# Output_Register_Electronic_Scheme_2021-1.net
KiCad netlist of a schematic drawn in Altium Designer
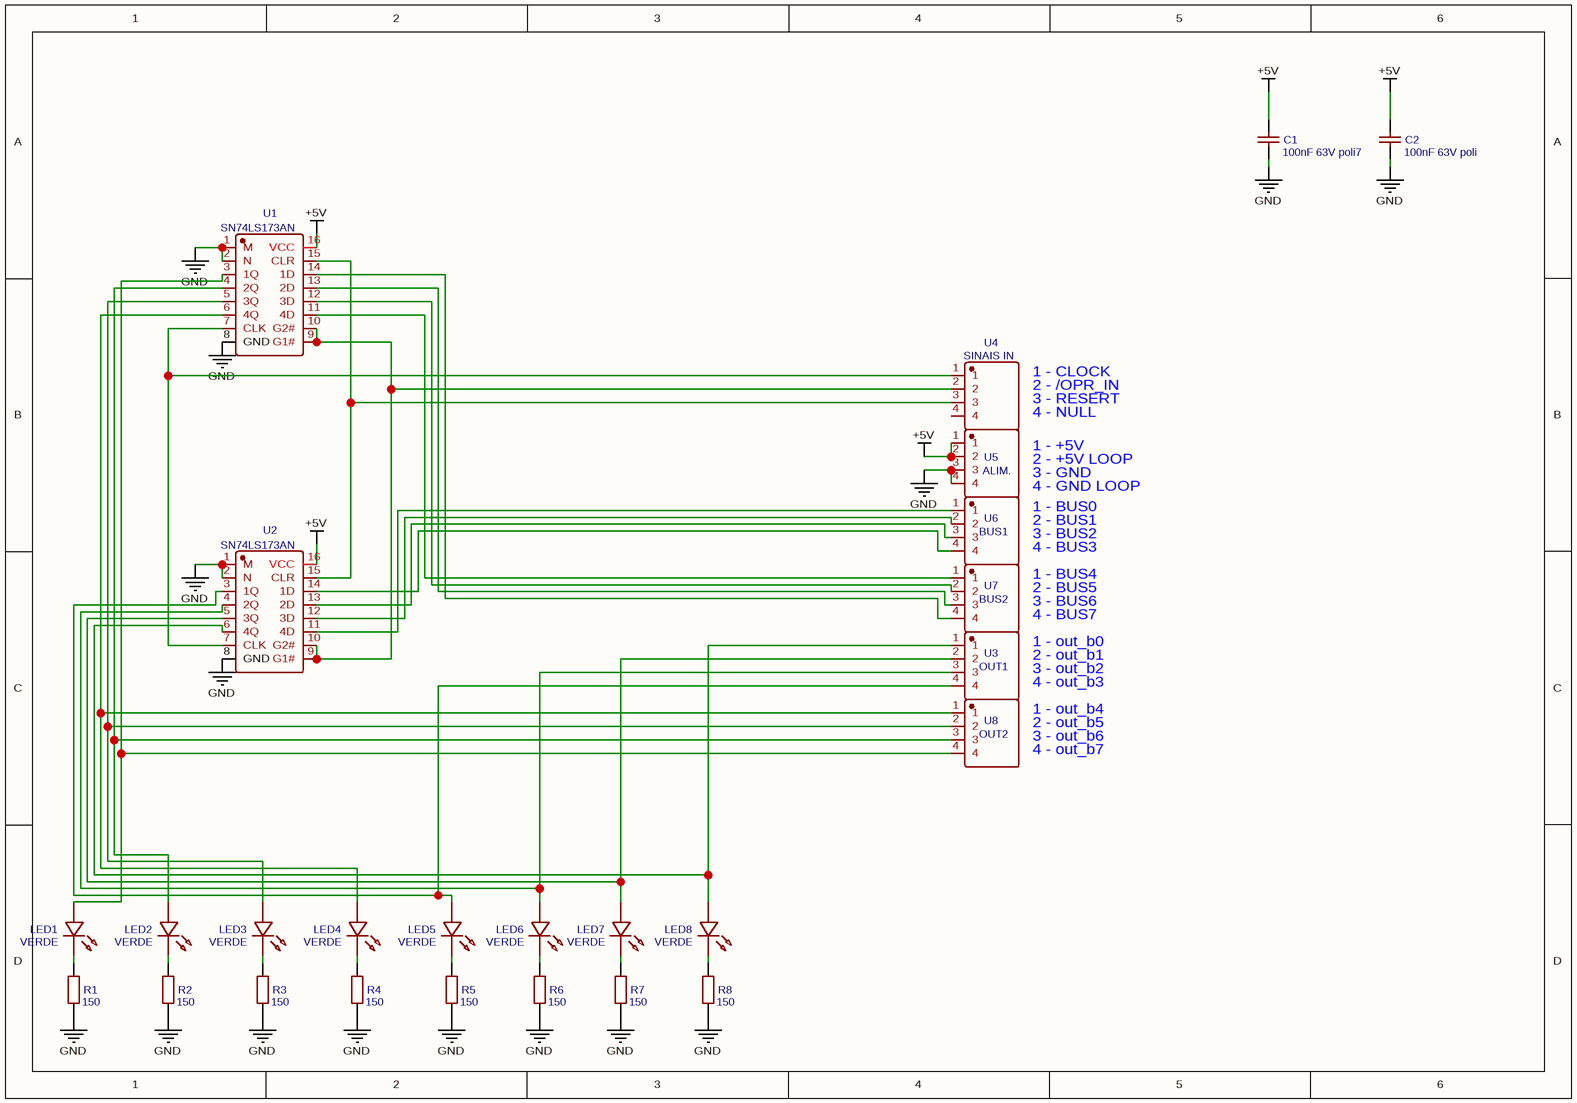
[diagram p0: Output Register Electronic Scheme_2021-10-31.schdoc]

(export (version "E")
  (design (tool "Eeschema 10.0.6"))
  (components
    (comp (ref "C1")
      (value "100nF 63V poli7")
      (fields
        (field (name "BOM_SUPPLIER PART") "C444741")
        (field (name "BOM_MANUFACTURER PART") "SR305C105KAR")
        (field (name "CONTRIBUTOR") "LCSC")
      )
      (libsource (lib "altium-import") (part "root_3_100nF 63V poli7_"))
    )
    (comp (ref "C2")
      (value "100nF 63V poli")
      (fields
        (field (name "BOM_SUPPLIER PART") "C444741")
        (field (name "BOM_MANUFACTURER PART") "SR305C105KAR")
        (field (name "CONTRIBUTOR") "LCSC")
      )
      (libsource (lib "altium-import") (part "root_3_100nF 63V poli_"))
    )
    (comp (ref "LED1")
      (value "VERDE")
      (fields
        (field (name "BOM_SUPPLIER PART") "C605465")
        (field (name "BOM_MANUFACTURER PART") "264-7GD")
        (field (name "CONTRIBUTOR") "LCSC")
      )
      (libsource (lib "altium-import") (part "root_1_VERDE_"))
    )
    (comp (ref "LED2")
      (value "VERDE")
      (fields
        (field (name "BOM_SUPPLIER PART") "C605465")
        (field (name "BOM_MANUFACTURER PART") "264-7GD")
        (field (name "CONTRIBUTOR") "LCSC")
      )
      (libsource (lib "altium-import") (part "root_1_VERDE_"))
    )
    (comp (ref "LED3")
      (value "VERDE")
      (fields
        (field (name "BOM_SUPPLIER PART") "C605465")
        (field (name "BOM_MANUFACTURER PART") "264-7GD")
        (field (name "CONTRIBUTOR") "LCSC")
      )
      (libsource (lib "altium-import") (part "root_1_VERDE_"))
    )
    (comp (ref "LED4")
      (value "VERDE")
      (fields
        (field (name "BOM_SUPPLIER PART") "C605465")
        (field (name "BOM_MANUFACTURER PART") "264-7GD")
        (field (name "CONTRIBUTOR") "LCSC")
      )
      (libsource (lib "altium-import") (part "root_1_VERDE_"))
    )
    (comp (ref "LED5")
      (value "VERDE")
      (fields
        (field (name "BOM_SUPPLIER PART") "C605465")
        (field (name "BOM_MANUFACTURER PART") "264-7GD")
        (field (name "CONTRIBUTOR") "LCSC")
      )
      (libsource (lib "altium-import") (part "root_1_VERDE_"))
    )
    (comp (ref "LED6")
      (value "VERDE")
      (fields
        (field (name "BOM_SUPPLIER PART") "C605465")
        (field (name "BOM_MANUFACTURER PART") "264-7GD")
        (field (name "CONTRIBUTOR") "LCSC")
      )
      (libsource (lib "altium-import") (part "root_1_VERDE_"))
    )
    (comp (ref "LED7")
      (value "VERDE")
      (fields
        (field (name "BOM_SUPPLIER PART") "C605465")
        (field (name "BOM_MANUFACTURER PART") "264-7GD")
        (field (name "CONTRIBUTOR") "LCSC")
      )
      (libsource (lib "altium-import") (part "root_1_VERDE_"))
    )
    (comp (ref "LED8")
      (value "VERDE")
      (fields
        (field (name "BOM_SUPPLIER PART") "C605465")
        (field (name "BOM_MANUFACTURER PART") "264-7GD")
        (field (name "CONTRIBUTOR") "LCSC")
      )
      (libsource (lib "altium-import") (part "root_1_VERDE_"))
    )
    (comp (ref "R1")
      (value "150")
      (fields
        (field (name "BOM_MANUFACTURER PART") "CFR02SJ0823A10")
        (field (name "BOM_SUPPLIER PART") "C69876")
      )
      (libsource (lib "altium-import") (part "root_3_150_"))
    )
    (comp (ref "R2")
      (value "150")
      (fields
        (field (name "BOM_MANUFACTURER PART") "CFR02SJ0823A10")
        (field (name "BOM_SUPPLIER PART") "C69876")
      )
      (libsource (lib "altium-import") (part "root_3_150_"))
    )
    (comp (ref "R3")
      (value "150")
      (fields
        (field (name "BOM_MANUFACTURER PART") "CFR02SJ0823A10")
        (field (name "BOM_SUPPLIER PART") "C69876")
      )
      (libsource (lib "altium-import") (part "root_3_150_"))
    )
    (comp (ref "R4")
      (value "150")
      (fields
        (field (name "BOM_MANUFACTURER PART") "CFR02SJ0823A10")
        (field (name "BOM_SUPPLIER PART") "C69876")
      )
      (libsource (lib "altium-import") (part "root_3_150_"))
    )
    (comp (ref "R5")
      (value "150")
      (fields
        (field (name "BOM_MANUFACTURER PART") "CFR02SJ0823A10")
        (field (name "BOM_SUPPLIER PART") "C69876")
      )
      (libsource (lib "altium-import") (part "root_3_150_"))
    )
    (comp (ref "R6")
      (value "150")
      (fields
        (field (name "BOM_MANUFACTURER PART") "CFR02SJ0823A10")
        (field (name "BOM_SUPPLIER PART") "C69876")
      )
      (libsource (lib "altium-import") (part "root_3_150_"))
    )
    (comp (ref "R7")
      (value "150")
      (fields
        (field (name "BOM_MANUFACTURER PART") "CFR02SJ0823A10")
        (field (name "BOM_SUPPLIER PART") "C69876")
      )
      (libsource (lib "altium-import") (part "root_3_150_"))
    )
    (comp (ref "R8")
      (value "150")
      (fields
        (field (name "BOM_MANUFACTURER PART") "CFR02SJ0823A10")
        (field (name "BOM_SUPPLIER PART") "C69876")
      )
      (libsource (lib "altium-import") (part "root_3_150_"))
    )
    (comp (ref "U1")
      (value "SN74LS173AN")
      (fields (field (name "BOM_SUPPLIER PART") "C1550125") (field (name "CONTRIBUTOR") "LCSC"))
      (libsource (lib "altium-import") (part "root_0_SN74LS173AN_"))
    )
    (comp (ref "U2")
      (value "SN74LS173AN")
      (fields (field (name "BOM_SUPPLIER PART") "C1550125") (field (name "CONTRIBUTOR") "LCSC"))
      (libsource (lib "altium-import") (part "root_0_SN74LS173AN_"))
    )
    (comp (ref "U3")
      (value "OUT1")
      (fields
        (field (name "BOM_SUPPLIER PART") "C210162")
        (field (name "BOM_MANUFACTURER PART") "171825-4")
        (field (name "CONTRIBUTOR") "LCSC")
      )
      (libsource (lib "altium-import") (part "root_0_OUT1_"))
    )
    (comp (ref "U4")
      (value "SINAIS IN")
      (fields
        (field (name "BOM_SUPPLIER PART") "C210162")
        (field (name "BOM_MANUFACTURER PART") "171825-4")
        (field (name "CONTRIBUTOR") "LCSC")
      )
      (libsource (lib "altium-import") (part "root_0_SINAIS IN_"))
    )
    (comp (ref "U5")
      (value "ALIM.")
      (fields
        (field (name "BOM_SUPPLIER PART") "C210162")
        (field (name "BOM_MANUFACTURER PART") "171825-4")
        (field (name "CONTRIBUTOR") "LCSC")
      )
      (libsource (lib "altium-import") (part "root_0_ALIM._"))
    )
    (comp (ref "U6")
      (value "BUS1")
      (fields
        (field (name "BOM_SUPPLIER PART") "C210162")
        (field (name "BOM_MANUFACTURER PART") "171825-4")
        (field (name "CONTRIBUTOR") "LCSC")
      )
      (libsource (lib "altium-import") (part "root_0_BUS1_"))
    )
    (comp (ref "U7")
      (value "BUS2")
      (fields
        (field (name "BOM_SUPPLIER PART") "C210162")
        (field (name "BOM_MANUFACTURER PART") "171825-4")
        (field (name "CONTRIBUTOR") "LCSC")
      )
      (libsource (lib "altium-import") (part "root_0_BUS2_"))
    )
    (comp (ref "U8")
      (value "OUT2")
      (fields
        (field (name "BOM_SUPPLIER PART") "C210162")
        (field (name "BOM_MANUFACTURER PART") "171825-4")
        (field (name "CONTRIBUTOR") "LCSC")
      )
      (libsource (lib "altium-import") (part "root_0_OUT2_"))
    )
  )
  (nets
    (net (code "1") (name "+5V") (class "Default")
      (node (ref "C1") (pin "1") (pinfunction "1_1") (pintype "passive"))
      (node (ref "C2") (pin "1") (pinfunction "1_1") (pintype "passive"))
      (node (ref "U1") (pin "16") (pinfunction "VCC_16") (pintype "passive"))
      (node (ref "U2") (pin "16") (pinfunction "VCC_16") (pintype "passive"))
      (node (ref "U5") (pin "1") (pinfunction "1_1") (pintype "passive"))
      (node (ref "U5") (pin "2") (pinfunction "2_2") (pintype "passive"))
    )
    (net (code "2") (name "GND") (class "Default")
      (node (ref "C1") (pin "2") (pinfunction "2_2") (pintype "passive"))
      (node (ref "C2") (pin "2") (pinfunction "2_2") (pintype "passive"))
      (node (ref "R1") (pin "2") (pinfunction "2_2") (pintype "passive"))
      (node (ref "R2") (pin "2") (pinfunction "2_2") (pintype "passive"))
      (node (ref "R3") (pin "2") (pinfunction "2_2") (pintype "passive"))
      (node (ref "R4") (pin "2") (pinfunction "2_2") (pintype "passive"))
      (node (ref "R5") (pin "2") (pinfunction "2_2") (pintype "passive"))
      (node (ref "R6") (pin "2") (pinfunction "2_2") (pintype "passive"))
      (node (ref "R7") (pin "2") (pinfunction "2_2") (pintype "passive"))
      (node (ref "R8") (pin "2") (pinfunction "2_2") (pintype "passive"))
      (node (ref "U1") (pin "1") (pinfunction "M_1") (pintype "passive"))
      (node (ref "U1") (pin "2") (pinfunction "N_2") (pintype "passive"))
      (node (ref "U1") (pin "8") (pinfunction "GND_8") (pintype "passive"))
      (node (ref "U2") (pin "1") (pinfunction "M_1") (pintype "passive"))
      (node (ref "U2") (pin "2") (pinfunction "N_2") (pintype "passive"))
      (node (ref "U2") (pin "8") (pinfunction "GND_8") (pintype "passive"))
      (node (ref "U5") (pin "3") (pinfunction "3_3") (pintype "passive"))
      (node (ref "U5") (pin "4") (pinfunction "4_4") (pintype "passive"))
    )
    (net (code "3") (name "Net-(LED1-+)") (class "Default")
      (node (ref "LED1") (pin "2") (pinfunction "+_2") (pintype "passive"))
      (node (ref "U1") (pin "3") (pinfunction "1Q_3") (pintype "passive"))
      (node (ref "U8") (pin "4") (pinfunction "4_4") (pintype "passive"))
    )
    (net (code "4") (name "Net-(LED1--)") (class "Default")
      (node (ref "LED1") (pin "1") (pinfunction "-_1") (pintype "passive"))
      (node (ref "R1") (pin "1") (pinfunction "1_1") (pintype "passive"))
    )
    (net (code "5") (name "Net-(LED2-+)") (class "Default")
      (node (ref "LED2") (pin "2") (pinfunction "+_2") (pintype "passive"))
      (node (ref "U1") (pin "4") (pinfunction "2Q_4") (pintype "passive"))
      (node (ref "U8") (pin "3") (pinfunction "3_3") (pintype "passive"))
    )
    (net (code "6") (name "Net-(LED2--)") (class "Default")
      (node (ref "LED2") (pin "1") (pinfunction "-_1") (pintype "passive"))
      (node (ref "R2") (pin "1") (pinfunction "1_1") (pintype "passive"))
    )
    (net (code "7") (name "Net-(LED3-+)") (class "Default")
      (node (ref "LED3") (pin "2") (pinfunction "+_2") (pintype "passive"))
      (node (ref "U1") (pin "5") (pinfunction "3Q_5") (pintype "passive"))
      (node (ref "U8") (pin "2") (pinfunction "2_2") (pintype "passive"))
    )
    (net (code "8") (name "Net-(LED3--)") (class "Default")
      (node (ref "LED3") (pin "1") (pinfunction "-_1") (pintype "passive"))
      (node (ref "R3") (pin "1") (pinfunction "1_1") (pintype "passive"))
    )
    (net (code "9") (name "Net-(LED4-+)") (class "Default")
      (node (ref "LED4") (pin "2") (pinfunction "+_2") (pintype "passive"))
      (node (ref "U1") (pin "6") (pinfunction "4Q_6") (pintype "passive"))
      (node (ref "U8") (pin "1") (pinfunction "1_1") (pintype "passive"))
    )
    (net (code "10") (name "Net-(LED4--)") (class "Default")
      (node (ref "LED4") (pin "1") (pinfunction "-_1") (pintype "passive"))
      (node (ref "R4") (pin "1") (pinfunction "1_1") (pintype "passive"))
    )
    (net (code "11") (name "Net-(LED5-+)") (class "Default")
      (node (ref "LED5") (pin "2") (pinfunction "+_2") (pintype "passive"))
      (node (ref "U2") (pin "3") (pinfunction "1Q_3") (pintype "passive"))
      (node (ref "U3") (pin "4") (pinfunction "4_4") (pintype "passive"))
    )
    (net (code "12") (name "Net-(LED5--)") (class "Default")
      (node (ref "LED5") (pin "1") (pinfunction "-_1") (pintype "passive"))
      (node (ref "R5") (pin "1") (pinfunction "1_1") (pintype "passive"))
    )
    (net (code "13") (name "Net-(LED6-+)") (class "Default")
      (node (ref "LED6") (pin "2") (pinfunction "+_2") (pintype "passive"))
      (node (ref "U2") (pin "4") (pinfunction "2Q_4") (pintype "passive"))
      (node (ref "U3") (pin "3") (pinfunction "3_3") (pintype "passive"))
    )
    (net (code "14") (name "Net-(LED6--)") (class "Default")
      (node (ref "LED6") (pin "1") (pinfunction "-_1") (pintype "passive"))
      (node (ref "R6") (pin "1") (pinfunction "1_1") (pintype "passive"))
    )
    (net (code "15") (name "Net-(LED7-+)") (class "Default")
      (node (ref "LED7") (pin "2") (pinfunction "+_2") (pintype "passive"))
      (node (ref "U2") (pin "5") (pinfunction "3Q_5") (pintype "passive"))
      (node (ref "U3") (pin "2") (pinfunction "2_2") (pintype "passive"))
    )
    (net (code "16") (name "Net-(LED7--)") (class "Default")
      (node (ref "LED7") (pin "1") (pinfunction "-_1") (pintype "passive"))
      (node (ref "R7") (pin "1") (pinfunction "1_1") (pintype "passive"))
    )
    (net (code "17") (name "Net-(LED8-+)") (class "Default")
      (node (ref "LED8") (pin "2") (pinfunction "+_2") (pintype "passive"))
      (node (ref "U2") (pin "6") (pinfunction "4Q_6") (pintype "passive"))
      (node (ref "U3") (pin "1") (pinfunction "1_1") (pintype "passive"))
    )
    (net (code "18") (name "Net-(LED8--)") (class "Default")
      (node (ref "LED8") (pin "1") (pinfunction "-_1") (pintype "passive"))
      (node (ref "R8") (pin "1") (pinfunction "1_1") (pintype "passive"))
    )
    (net (code "19") (name "Net-(U1-1D)") (class "Default")
      (node (ref "U1") (pin "14") (pinfunction "1D_14") (pintype "passive"))
      (node (ref "U7") (pin "4") (pinfunction "4_4") (pintype "passive"))
    )
    (net (code "20") (name "Net-(U1-2D)") (class "Default")
      (node (ref "U1") (pin "13") (pinfunction "2D_13") (pintype "passive"))
      (node (ref "U7") (pin "3") (pinfunction "3_3") (pintype "passive"))
    )
    (net (code "21") (name "Net-(U1-3D)") (class "Default")
      (node (ref "U1") (pin "12") (pinfunction "3D_12") (pintype "passive"))
      (node (ref "U7") (pin "2") (pinfunction "2_2") (pintype "passive"))
    )
    (net (code "22") (name "Net-(U1-4D)") (class "Default")
      (node (ref "U1") (pin "11") (pinfunction "4D_11") (pintype "passive"))
      (node (ref "U7") (pin "1") (pinfunction "1_1") (pintype "passive"))
    )
    (net (code "23") (name "Net-(U1-CLK)") (class "Default")
      (node (ref "U1") (pin "7") (pinfunction "CLK_7") (pintype "passive"))
      (node (ref "U2") (pin "7") (pinfunction "CLK_7") (pintype "passive"))
      (node (ref "U4") (pin "1") (pinfunction "1_1") (pintype "passive"))
    )
    (net (code "24") (name "Net-(U1-CLR)") (class "Default")
      (node (ref "U1") (pin "15") (pinfunction "CLR_15") (pintype "passive"))
      (node (ref "U2") (pin "15") (pinfunction "CLR_15") (pintype "passive"))
      (node (ref "U4") (pin "3") (pinfunction "3_3") (pintype "passive"))
    )
    (net (code "25") (name "Net-(U1-G1#)") (class "Default")
      (node (ref "U1") (pin "10") (pinfunction "G2#_10") (pintype "passive"))
      (node (ref "U1") (pin "9") (pinfunction "G1#_9") (pintype "passive"))
      (node (ref "U2") (pin "10") (pinfunction "G2#_10") (pintype "passive"))
      (node (ref "U2") (pin "9") (pinfunction "G1#_9") (pintype "passive"))
      (node (ref "U4") (pin "2") (pinfunction "2_2") (pintype "passive"))
    )
    (net (code "26") (name "Net-(U2-1D)") (class "Default")
      (node (ref "U2") (pin "14") (pinfunction "1D_14") (pintype "passive"))
      (node (ref "U6") (pin "4") (pinfunction "4_4") (pintype "passive"))
    )
    (net (code "27") (name "Net-(U2-2D)") (class "Default")
      (node (ref "U2") (pin "13") (pinfunction "2D_13") (pintype "passive"))
      (node (ref "U6") (pin "3") (pinfunction "3_3") (pintype "passive"))
    )
    (net (code "28") (name "Net-(U2-3D)") (class "Default")
      (node (ref "U2") (pin "12") (pinfunction "3D_12") (pintype "passive"))
      (node (ref "U6") (pin "2") (pinfunction "2_2") (pintype "passive"))
    )
    (net (code "29") (name "Net-(U2-4D)") (class "Default")
      (node (ref "U2") (pin "11") (pinfunction "4D_11") (pintype "passive"))
      (node (ref "U6") (pin "1") (pinfunction "1_1") (pintype "passive"))
    )
    (net (code "30") (name "unconnected-(U4-Pad4)") (class "Default")
      (node (ref "U4") (pin "4") (pinfunction "4_4") (pintype "passive"))
    )
  )
)
